# pwmdrive_2014_001.net
KiCad netlist of a schematic drawn in EAGLE
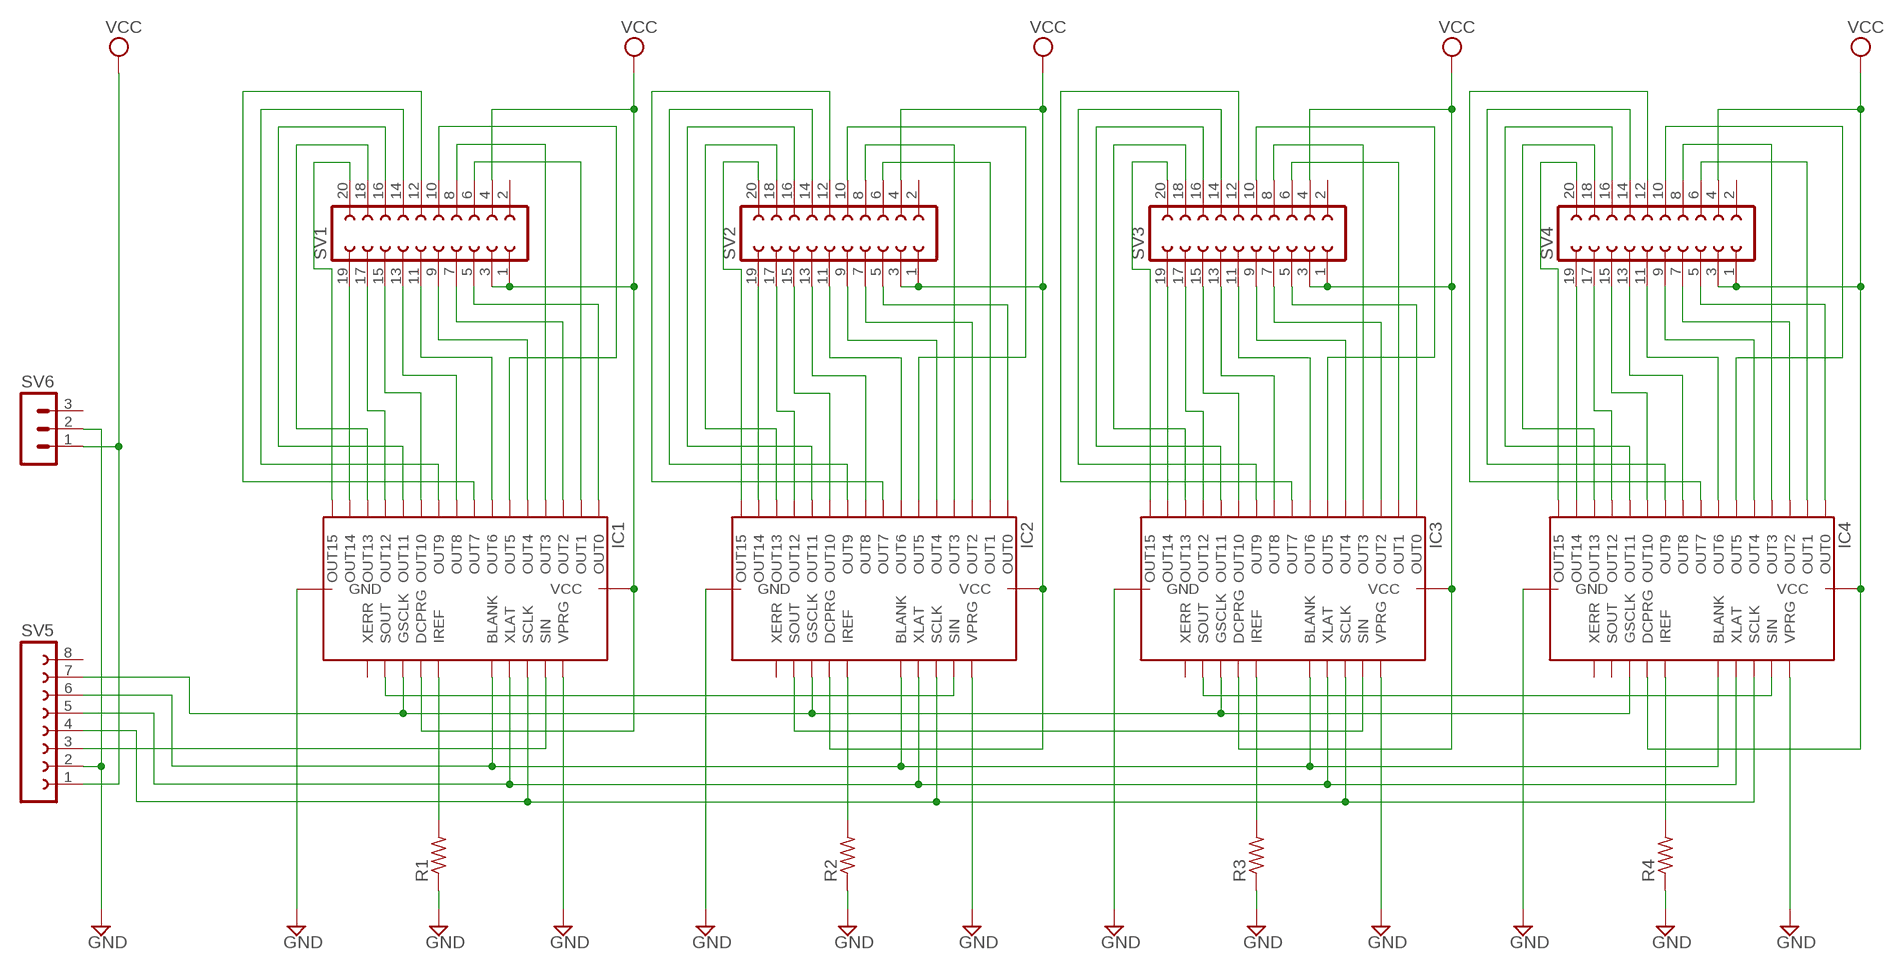
[diagram p0: schematic, sheet 1]

(export (version "E")
  (design (tool "Eeschema 10.0.6"))
  (components
    (comp (ref "IC1")
      (value "IC-PACKAGE_DIL28")
      (footprint "eagle-import:IC-PACKAGE_DIL28-6")
      (libsource (lib "eagle-import") (part "IC-PACKAGE_DIL28"))
    )
    (comp (ref "IC2")
      (value "IC-PACKAGE_DIL28")
      (footprint "eagle-import:IC-PACKAGE_DIL28-6")
      (libsource (lib "eagle-import") (part "IC-PACKAGE_DIL28"))
    )
    (comp (ref "IC3")
      (value "IC-PACKAGE_DIL28")
      (footprint "eagle-import:IC-PACKAGE_DIL28-6")
      (libsource (lib "eagle-import") (part "IC-PACKAGE_DIL28"))
    )
    (comp (ref "IC4")
      (value "IC-PACKAGE_DIL28")
      (footprint "eagle-import:IC-PACKAGE_DIL28-6")
      (libsource (lib "eagle-import") (part "IC-PACKAGE_DIL28"))
    )
    (comp (ref "R1")
      (value "R-US_0204/7")
      (footprint "eagle-import:0204_7")
      (libsource (lib "eagle-import") (part "R-US_0204/7"))
    )
    (comp (ref "R2")
      (value "R-US_0204/7")
      (footprint "eagle-import:0204_7")
      (libsource (lib "eagle-import") (part "R-US_0204/7"))
    )
    (comp (ref "R3")
      (value "R-US_0204/7")
      (footprint "eagle-import:0204_7")
      (libsource (lib "eagle-import") (part "R-US_0204/7"))
    )
    (comp (ref "R4")
      (value "R-US_0204/7")
      (footprint "eagle-import:0204_7")
      (libsource (lib "eagle-import") (part "R-US_0204/7"))
    )
    (comp (ref "SV1")
      (value "FE10-2")
      (footprint "eagle-import:FE10-2")
      (libsource (lib "eagle-import") (part "FE10-2"))
    )
    (comp (ref "SV2")
      (value "FE10-2")
      (footprint "eagle-import:FE10-2")
      (libsource (lib "eagle-import") (part "FE10-2"))
    )
    (comp (ref "SV3")
      (value "FE10-2")
      (footprint "eagle-import:FE10-2")
      (libsource (lib "eagle-import") (part "FE10-2"))
    )
    (comp (ref "SV4")
      (value "FE10-2")
      (footprint "eagle-import:FE10-2")
      (libsource (lib "eagle-import") (part "FE10-2"))
    )
    (comp (ref "SV5")
      (value "FE08-1")
      (footprint "eagle-import:FE08")
      (libsource (lib "eagle-import") (part "FE08-1"))
    )
    (comp (ref "SV6")
      (value "MA03-1")
      (footprint "eagle-import:MA03-1")
      (libsource (lib "eagle-import") (part "MA03-1"))
    )
  )
  (nets
    (net (code "1") (name "GND") (class "Default")
      (node (ref "IC1") (pin "22") (pinfunction "GND_22") (pintype "power_in"))
      (node (ref "IC1") (pin "27") (pinfunction "VPRG_27") (pintype "input"))
      (node (ref "IC2") (pin "22") (pinfunction "GND_22") (pintype "power_in"))
      (node (ref "IC2") (pin "27") (pinfunction "VPRG_27") (pintype "input"))
      (node (ref "IC3") (pin "22") (pinfunction "GND_22") (pintype "power_in"))
      (node (ref "IC3") (pin "27") (pinfunction "VPRG_27") (pintype "input"))
      (node (ref "IC4") (pin "22") (pinfunction "GND_22") (pintype "power_in"))
      (node (ref "IC4") (pin "27") (pinfunction "VPRG_27") (pintype "input"))
      (node (ref "R1") (pin "1") (pinfunction "1_1") (pintype "passive"))
      (node (ref "R2") (pin "1") (pinfunction "1_1") (pintype "passive"))
      (node (ref "R3") (pin "1") (pinfunction "1_1") (pintype "passive"))
      (node (ref "R4") (pin "1") (pinfunction "1_1") (pintype "passive"))
      (node (ref "SV5") (pin "2") (pinfunction "2_2") (pintype "passive"))
      (node (ref "SV6") (pin "2") (pinfunction "2_2") (pintype "passive"))
    )
    (net (code "2") (name "Net-(IC1-BLANK)") (class "Default")
      (node (ref "IC1") (pin "23") (pinfunction "BLANK_23") (pintype "input"))
      (node (ref "IC2") (pin "23") (pinfunction "BLANK_23") (pintype "input"))
      (node (ref "IC3") (pin "23") (pinfunction "BLANK_23") (pintype "input"))
      (node (ref "IC4") (pin "23") (pinfunction "BLANK_23") (pintype "input"))
      (node (ref "SV5") (pin "6") (pinfunction "6_6") (pintype "passive"))
    )
    (net (code "3") (name "Net-(IC1-GSCLK)") (class "Default")
      (node (ref "IC1") (pin "18") (pinfunction "GSCLK_18") (pintype "input"))
      (node (ref "IC2") (pin "18") (pinfunction "GSCLK_18") (pintype "input"))
      (node (ref "IC3") (pin "18") (pinfunction "GSCLK_18") (pintype "input"))
      (node (ref "IC4") (pin "18") (pinfunction "GSCLK_18") (pintype "input"))
      (node (ref "SV5") (pin "7") (pinfunction "7_7") (pintype "passive"))
    )
    (net (code "4") (name "Net-(IC1-IREF)") (class "Default")
      (node (ref "IC1") (pin "20") (pinfunction "IREF_20") (pintype "passive"))
      (node (ref "R1") (pin "2") (pinfunction "2_2") (pintype "passive"))
    )
    (net (code "5") (name "Net-(IC1-OUT0)") (class "Default")
      (node (ref "IC1") (pin "28") (pinfunction "OUT0_28") (pintype "open_collector"))
      (node (ref "SV1") (pin "5") (pinfunction "5_5") (pintype "passive"))
    )
    (net (code "6") (name "Net-(IC1-OUT1)") (class "Default")
      (node (ref "IC1") (pin "1") (pinfunction "OUT1_1") (pintype "open_collector"))
      (node (ref "SV1") (pin "6") (pinfunction "6_6") (pintype "passive"))
    )
    (net (code "7") (name "Net-(IC1-OUT2)") (class "Default")
      (node (ref "IC1") (pin "2") (pinfunction "OUT2_2") (pintype "open_collector"))
      (node (ref "SV1") (pin "7") (pinfunction "7_7") (pintype "passive"))
    )
    (net (code "8") (name "Net-(IC1-OUT3)") (class "Default")
      (node (ref "IC1") (pin "3") (pinfunction "OUT3_3") (pintype "open_collector"))
      (node (ref "SV1") (pin "8") (pinfunction "8_8") (pintype "passive"))
    )
    (net (code "9") (name "Net-(IC1-OUT4)") (class "Default")
      (node (ref "IC1") (pin "4") (pinfunction "OUT4_4") (pintype "open_collector"))
      (node (ref "SV1") (pin "9") (pinfunction "9_9") (pintype "passive"))
    )
    (net (code "10") (name "Net-(IC1-OUT5)") (class "Default")
      (node (ref "IC1") (pin "5") (pinfunction "OUT5_5") (pintype "open_collector"))
      (node (ref "SV1") (pin "10") (pinfunction "10_10") (pintype "passive"))
    )
    (net (code "11") (name "Net-(IC1-OUT6)") (class "Default")
      (node (ref "IC1") (pin "6") (pinfunction "OUT6_6") (pintype "open_collector"))
      (node (ref "SV1") (pin "11") (pinfunction "11_11") (pintype "passive"))
    )
    (net (code "12") (name "Net-(IC1-OUT7)") (class "Default")
      (node (ref "IC1") (pin "7") (pinfunction "OUT7_7") (pintype "open_collector"))
      (node (ref "SV1") (pin "12") (pinfunction "12_12") (pintype "passive"))
    )
    (net (code "13") (name "Net-(IC1-OUT8)") (class "Default")
      (node (ref "IC1") (pin "8") (pinfunction "OUT8_8") (pintype "open_collector"))
      (node (ref "SV1") (pin "13") (pinfunction "13_13") (pintype "passive"))
    )
    (net (code "14") (name "Net-(IC1-OUT9)") (class "Default")
      (node (ref "IC1") (pin "9") (pinfunction "OUT9_9") (pintype "open_collector"))
      (node (ref "SV1") (pin "14") (pinfunction "14_14") (pintype "passive"))
    )
    (net (code "15") (name "Net-(IC1-OUT10)") (class "Default")
      (node (ref "IC1") (pin "10") (pinfunction "OUT10_10") (pintype "open_collector"))
      (node (ref "SV1") (pin "15") (pinfunction "15_15") (pintype "passive"))
    )
    (net (code "16") (name "Net-(IC1-OUT11)") (class "Default")
      (node (ref "IC1") (pin "11") (pinfunction "OUT11_11") (pintype "open_collector"))
      (node (ref "SV1") (pin "16") (pinfunction "16_16") (pintype "passive"))
    )
    (net (code "17") (name "Net-(IC1-OUT12)") (class "Default")
      (node (ref "IC1") (pin "12") (pinfunction "OUT12_12") (pintype "open_collector"))
      (node (ref "SV1") (pin "17") (pinfunction "17_17") (pintype "passive"))
    )
    (net (code "18") (name "Net-(IC1-OUT13)") (class "Default")
      (node (ref "IC1") (pin "13") (pinfunction "OUT13_13") (pintype "open_collector"))
      (node (ref "SV1") (pin "18") (pinfunction "18_18") (pintype "passive"))
    )
    (net (code "19") (name "Net-(IC1-OUT14)") (class "Default")
      (node (ref "IC1") (pin "14") (pinfunction "OUT14_14") (pintype "open_collector"))
      (node (ref "SV1") (pin "19") (pinfunction "19_19") (pintype "passive"))
    )
    (net (code "20") (name "Net-(IC1-OUT15)") (class "Default")
      (node (ref "IC1") (pin "15") (pinfunction "OUT15_15") (pintype "open_collector"))
      (node (ref "SV1") (pin "20") (pinfunction "20_20") (pintype "passive"))
    )
    (net (code "21") (name "Net-(IC1-SCLK)") (class "Default")
      (node (ref "IC1") (pin "25") (pinfunction "SCLK_25") (pintype "input"))
      (node (ref "IC2") (pin "25") (pinfunction "SCLK_25") (pintype "input"))
      (node (ref "IC3") (pin "25") (pinfunction "SCLK_25") (pintype "input"))
      (node (ref "IC4") (pin "25") (pinfunction "SCLK_25") (pintype "input"))
      (node (ref "SV5") (pin "4") (pinfunction "4_4") (pintype "passive"))
    )
    (net (code "22") (name "Net-(IC1-SIN)") (class "Default")
      (node (ref "IC1") (pin "26") (pinfunction "SIN_26") (pintype "input"))
      (node (ref "SV5") (pin "3") (pinfunction "3_3") (pintype "passive"))
    )
    (net (code "23") (name "Net-(IC1-SOUT)") (class "Default")
      (node (ref "IC1") (pin "17") (pinfunction "SOUT_17") (pintype "output"))
      (node (ref "IC2") (pin "26") (pinfunction "SIN_26") (pintype "input"))
    )
    (net (code "24") (name "Net-(IC1-XLAT)") (class "Default")
      (node (ref "IC1") (pin "24") (pinfunction "XLAT_24") (pintype "input"))
      (node (ref "IC2") (pin "24") (pinfunction "XLAT_24") (pintype "input"))
      (node (ref "IC3") (pin "24") (pinfunction "XLAT_24") (pintype "input"))
      (node (ref "IC4") (pin "24") (pinfunction "XLAT_24") (pintype "input"))
      (node (ref "SV5") (pin "5") (pinfunction "5_5") (pintype "passive"))
    )
    (net (code "25") (name "Net-(IC2-IREF)") (class "Default")
      (node (ref "IC2") (pin "20") (pinfunction "IREF_20") (pintype "passive"))
      (node (ref "R2") (pin "2") (pinfunction "2_2") (pintype "passive"))
    )
    (net (code "26") (name "Net-(IC2-OUT0)") (class "Default")
      (node (ref "IC2") (pin "28") (pinfunction "OUT0_28") (pintype "open_collector"))
      (node (ref "SV2") (pin "5") (pinfunction "5_5") (pintype "passive"))
    )
    (net (code "27") (name "Net-(IC2-OUT1)") (class "Default")
      (node (ref "IC2") (pin "1") (pinfunction "OUT1_1") (pintype "open_collector"))
      (node (ref "SV2") (pin "6") (pinfunction "6_6") (pintype "passive"))
    )
    (net (code "28") (name "Net-(IC2-OUT2)") (class "Default")
      (node (ref "IC2") (pin "2") (pinfunction "OUT2_2") (pintype "open_collector"))
      (node (ref "SV2") (pin "7") (pinfunction "7_7") (pintype "passive"))
    )
    (net (code "29") (name "Net-(IC2-OUT3)") (class "Default")
      (node (ref "IC2") (pin "3") (pinfunction "OUT3_3") (pintype "open_collector"))
      (node (ref "SV2") (pin "8") (pinfunction "8_8") (pintype "passive"))
    )
    (net (code "30") (name "Net-(IC2-OUT4)") (class "Default")
      (node (ref "IC2") (pin "4") (pinfunction "OUT4_4") (pintype "open_collector"))
      (node (ref "SV2") (pin "9") (pinfunction "9_9") (pintype "passive"))
    )
    (net (code "31") (name "Net-(IC2-OUT5)") (class "Default")
      (node (ref "IC2") (pin "5") (pinfunction "OUT5_5") (pintype "open_collector"))
      (node (ref "SV2") (pin "10") (pinfunction "10_10") (pintype "passive"))
    )
    (net (code "32") (name "Net-(IC2-OUT6)") (class "Default")
      (node (ref "IC2") (pin "6") (pinfunction "OUT6_6") (pintype "open_collector"))
      (node (ref "SV2") (pin "11") (pinfunction "11_11") (pintype "passive"))
    )
    (net (code "33") (name "Net-(IC2-OUT7)") (class "Default")
      (node (ref "IC2") (pin "7") (pinfunction "OUT7_7") (pintype "open_collector"))
      (node (ref "SV2") (pin "12") (pinfunction "12_12") (pintype "passive"))
    )
    (net (code "34") (name "Net-(IC2-OUT8)") (class "Default")
      (node (ref "IC2") (pin "8") (pinfunction "OUT8_8") (pintype "open_collector"))
      (node (ref "SV2") (pin "13") (pinfunction "13_13") (pintype "passive"))
    )
    (net (code "35") (name "Net-(IC2-OUT9)") (class "Default")
      (node (ref "IC2") (pin "9") (pinfunction "OUT9_9") (pintype "open_collector"))
      (node (ref "SV2") (pin "14") (pinfunction "14_14") (pintype "passive"))
    )
    (net (code "36") (name "Net-(IC2-OUT10)") (class "Default")
      (node (ref "IC2") (pin "10") (pinfunction "OUT10_10") (pintype "open_collector"))
      (node (ref "SV2") (pin "15") (pinfunction "15_15") (pintype "passive"))
    )
    (net (code "37") (name "Net-(IC2-OUT11)") (class "Default")
      (node (ref "IC2") (pin "11") (pinfunction "OUT11_11") (pintype "open_collector"))
      (node (ref "SV2") (pin "16") (pinfunction "16_16") (pintype "passive"))
    )
    (net (code "38") (name "Net-(IC2-OUT12)") (class "Default")
      (node (ref "IC2") (pin "12") (pinfunction "OUT12_12") (pintype "open_collector"))
      (node (ref "SV2") (pin "17") (pinfunction "17_17") (pintype "passive"))
    )
    (net (code "39") (name "Net-(IC2-OUT13)") (class "Default")
      (node (ref "IC2") (pin "13") (pinfunction "OUT13_13") (pintype "open_collector"))
      (node (ref "SV2") (pin "18") (pinfunction "18_18") (pintype "passive"))
    )
    (net (code "40") (name "Net-(IC2-OUT14)") (class "Default")
      (node (ref "IC2") (pin "14") (pinfunction "OUT14_14") (pintype "open_collector"))
      (node (ref "SV2") (pin "19") (pinfunction "19_19") (pintype "passive"))
    )
    (net (code "41") (name "Net-(IC2-OUT15)") (class "Default")
      (node (ref "IC2") (pin "15") (pinfunction "OUT15_15") (pintype "open_collector"))
      (node (ref "SV2") (pin "20") (pinfunction "20_20") (pintype "passive"))
    )
    (net (code "42") (name "Net-(IC2-SOUT)") (class "Default")
      (node (ref "IC2") (pin "17") (pinfunction "SOUT_17") (pintype "output"))
      (node (ref "IC3") (pin "26") (pinfunction "SIN_26") (pintype "input"))
    )
    (net (code "43") (name "Net-(IC3-IREF)") (class "Default")
      (node (ref "IC3") (pin "20") (pinfunction "IREF_20") (pintype "passive"))
      (node (ref "R3") (pin "2") (pinfunction "2_2") (pintype "passive"))
    )
    (net (code "44") (name "Net-(IC3-OUT0)") (class "Default")
      (node (ref "IC3") (pin "28") (pinfunction "OUT0_28") (pintype "open_collector"))
      (node (ref "SV3") (pin "5") (pinfunction "5_5") (pintype "passive"))
    )
    (net (code "45") (name "Net-(IC3-OUT1)") (class "Default")
      (node (ref "IC3") (pin "1") (pinfunction "OUT1_1") (pintype "open_collector"))
      (node (ref "SV3") (pin "6") (pinfunction "6_6") (pintype "passive"))
    )
    (net (code "46") (name "Net-(IC3-OUT2)") (class "Default")
      (node (ref "IC3") (pin "2") (pinfunction "OUT2_2") (pintype "open_collector"))
      (node (ref "SV3") (pin "7") (pinfunction "7_7") (pintype "passive"))
    )
    (net (code "47") (name "Net-(IC3-OUT3)") (class "Default")
      (node (ref "IC3") (pin "3") (pinfunction "OUT3_3") (pintype "open_collector"))
      (node (ref "SV3") (pin "8") (pinfunction "8_8") (pintype "passive"))
    )
    (net (code "48") (name "Net-(IC3-OUT4)") (class "Default")
      (node (ref "IC3") (pin "4") (pinfunction "OUT4_4") (pintype "open_collector"))
      (node (ref "SV3") (pin "9") (pinfunction "9_9") (pintype "passive"))
    )
    (net (code "49") (name "Net-(IC3-OUT5)") (class "Default")
      (node (ref "IC3") (pin "5") (pinfunction "OUT5_5") (pintype "open_collector"))
      (node (ref "SV3") (pin "10") (pinfunction "10_10") (pintype "passive"))
    )
    (net (code "50") (name "Net-(IC3-OUT6)") (class "Default")
      (node (ref "IC3") (pin "6") (pinfunction "OUT6_6") (pintype "open_collector"))
      (node (ref "SV3") (pin "11") (pinfunction "11_11") (pintype "passive"))
    )
    (net (code "51") (name "Net-(IC3-OUT7)") (class "Default")
      (node (ref "IC3") (pin "7") (pinfunction "OUT7_7") (pintype "open_collector"))
      (node (ref "SV3") (pin "12") (pinfunction "12_12") (pintype "passive"))
    )
    (net (code "52") (name "Net-(IC3-OUT8)") (class "Default")
      (node (ref "IC3") (pin "8") (pinfunction "OUT8_8") (pintype "open_collector"))
      (node (ref "SV3") (pin "13") (pinfunction "13_13") (pintype "passive"))
    )
    (net (code "53") (name "Net-(IC3-OUT9)") (class "Default")
      (node (ref "IC3") (pin "9") (pinfunction "OUT9_9") (pintype "open_collector"))
      (node (ref "SV3") (pin "14") (pinfunction "14_14") (pintype "passive"))
    )
    (net (code "54") (name "Net-(IC3-OUT10)") (class "Default")
      (node (ref "IC3") (pin "10") (pinfunction "OUT10_10") (pintype "open_collector"))
      (node (ref "SV3") (pin "15") (pinfunction "15_15") (pintype "passive"))
    )
    (net (code "55") (name "Net-(IC3-OUT11)") (class "Default")
      (node (ref "IC3") (pin "11") (pinfunction "OUT11_11") (pintype "open_collector"))
      (node (ref "SV3") (pin "16") (pinfunction "16_16") (pintype "passive"))
    )
    (net (code "56") (name "Net-(IC3-OUT12)") (class "Default")
      (node (ref "IC3") (pin "12") (pinfunction "OUT12_12") (pintype "open_collector"))
      (node (ref "SV3") (pin "17") (pinfunction "17_17") (pintype "passive"))
    )
    (net (code "57") (name "Net-(IC3-OUT13)") (class "Default")
      (node (ref "IC3") (pin "13") (pinfunction "OUT13_13") (pintype "open_collector"))
      (node (ref "SV3") (pin "18") (pinfunction "18_18") (pintype "passive"))
    )
    (net (code "58") (name "Net-(IC3-OUT14)") (class "Default")
      (node (ref "IC3") (pin "14") (pinfunction "OUT14_14") (pintype "open_collector"))
      (node (ref "SV3") (pin "19") (pinfunction "19_19") (pintype "passive"))
    )
    (net (code "59") (name "Net-(IC3-OUT15)") (class "Default")
      (node (ref "IC3") (pin "15") (pinfunction "OUT15_15") (pintype "open_collector"))
      (node (ref "SV3") (pin "20") (pinfunction "20_20") (pintype "passive"))
    )
    (net (code "60") (name "Net-(IC3-SOUT)") (class "Default")
      (node (ref "IC3") (pin "17") (pinfunction "SOUT_17") (pintype "output"))
      (node (ref "IC4") (pin "26") (pinfunction "SIN_26") (pintype "input"))
    )
    (net (code "61") (name "Net-(IC4-IREF)") (class "Default")
      (node (ref "IC4") (pin "20") (pinfunction "IREF_20") (pintype "passive"))
      (node (ref "R4") (pin "2") (pinfunction "2_2") (pintype "passive"))
    )
    (net (code "62") (name "Net-(IC4-OUT0)") (class "Default")
      (node (ref "IC4") (pin "28") (pinfunction "OUT0_28") (pintype "open_collector"))
      (node (ref "SV4") (pin "5") (pinfunction "5_5") (pintype "passive"))
    )
    (net (code "63") (name "Net-(IC4-OUT1)") (class "Default")
      (node (ref "IC4") (pin "1") (pinfunction "OUT1_1") (pintype "open_collector"))
      (node (ref "SV4") (pin "6") (pinfunction "6_6") (pintype "passive"))
    )
    (net (code "64") (name "Net-(IC4-OUT2)") (class "Default")
      (node (ref "IC4") (pin "2") (pinfunction "OUT2_2") (pintype "open_collector"))
      (node (ref "SV4") (pin "7") (pinfunction "7_7") (pintype "passive"))
    )
    (net (code "65") (name "Net-(IC4-OUT3)") (class "Default")
      (node (ref "IC4") (pin "3") (pinfunction "OUT3_3") (pintype "open_collector"))
      (node (ref "SV4") (pin "8") (pinfunction "8_8") (pintype "passive"))
    )
    (net (code "66") (name "Net-(IC4-OUT4)") (class "Default")
      (node (ref "IC4") (pin "4") (pinfunction "OUT4_4") (pintype "open_collector"))
      (node (ref "SV4") (pin "9") (pinfunction "9_9") (pintype "passive"))
    )
    (net (code "67") (name "Net-(IC4-OUT5)") (class "Default")
      (node (ref "IC4") (pin "5") (pinfunction "OUT5_5") (pintype "open_collector"))
      (node (ref "SV4") (pin "10") (pinfunction "10_10") (pintype "passive"))
    )
    (net (code "68") (name "Net-(IC4-OUT6)") (class "Default")
      (node (ref "IC4") (pin "6") (pinfunction "OUT6_6") (pintype "open_collector"))
      (node (ref "SV4") (pin "11") (pinfunction "11_11") (pintype "passive"))
    )
    (net (code "69") (name "Net-(IC4-OUT7)") (class "Default")
      (node (ref "IC4") (pin "7") (pinfunction "OUT7_7") (pintype "open_collector"))
      (node (ref "SV4") (pin "12") (pinfunction "12_12") (pintype "passive"))
    )
    (net (code "70") (name "Net-(IC4-OUT8)") (class "Default")
      (node (ref "IC4") (pin "8") (pinfunction "OUT8_8") (pintype "open_collector"))
      (node (ref "SV4") (pin "13") (pinfunction "13_13") (pintype "passive"))
    )
    (net (code "71") (name "Net-(IC4-OUT9)") (class "Default")
      (node (ref "IC4") (pin "9") (pinfunction "OUT9_9") (pintype "open_collector"))
      (node (ref "SV4") (pin "14") (pinfunction "14_14") (pintype "passive"))
    )
    (net (code "72") (name "Net-(IC4-OUT10)") (class "Default")
      (node (ref "IC4") (pin "10") (pinfunction "OUT10_10") (pintype "open_collector"))
      (node (ref "SV4") (pin "15") (pinfunction "15_15") (pintype "passive"))
    )
    (net (code "73") (name "Net-(IC4-OUT11)") (class "Default")
      (node (ref "IC4") (pin "11") (pinfunction "OUT11_11") (pintype "open_collector"))
      (node (ref "SV4") (pin "16") (pinfunction "16_16") (pintype "passive"))
    )
    (net (code "74") (name "Net-(IC4-OUT12)") (class "Default")
      (node (ref "IC4") (pin "12") (pinfunction "OUT12_12") (pintype "open_collector"))
      (node (ref "SV4") (pin "17") (pinfunction "17_17") (pintype "passive"))
    )
    (net (code "75") (name "Net-(IC4-OUT13)") (class "Default")
      (node (ref "IC4") (pin "13") (pinfunction "OUT13_13") (pintype "open_collector"))
      (node (ref "SV4") (pin "18") (pinfunction "18_18") (pintype "passive"))
    )
    (net (code "76") (name "Net-(IC4-OUT14)") (class "Default")
      (node (ref "IC4") (pin "14") (pinfunction "OUT14_14") (pintype "open_collector"))
      (node (ref "SV4") (pin "19") (pinfunction "19_19") (pintype "passive"))
    )
    (net (code "77") (name "Net-(IC4-OUT15)") (class "Default")
      (node (ref "IC4") (pin "15") (pinfunction "OUT15_15") (pintype "open_collector"))
      (node (ref "SV4") (pin "20") (pinfunction "20_20") (pintype "passive"))
    )
    (net (code "78") (name "VCC") (class "Default")
      (node (ref "IC1") (pin "19") (pinfunction "DCPRG_19") (pintype "input"))
      (node (ref "IC1") (pin "21") (pinfunction "VCC_21") (pintype "power_in"))
      (node (ref "IC2") (pin "19") (pinfunction "DCPRG_19") (pintype "input"))
      (node (ref "IC2") (pin "21") (pinfunction "VCC_21") (pintype "power_in"))
      (node (ref "IC3") (pin "19") (pinfunction "DCPRG_19") (pintype "input"))
      (node (ref "IC3") (pin "21") (pinfunction "VCC_21") (pintype "power_in"))
      (node (ref "IC4") (pin "19") (pinfunction "DCPRG_19") (pintype "input"))
      (node (ref "IC4") (pin "21") (pinfunction "VCC_21") (pintype "power_in"))
      (node (ref "SV1") (pin "1") (pinfunction "1_1") (pintype "passive"))
      (node (ref "SV1") (pin "3") (pinfunction "3_3") (pintype "passive"))
      (node (ref "SV1") (pin "4") (pinfunction "4_4") (pintype "passive"))
      (node (ref "SV2") (pin "1") (pinfunction "1_1") (pintype "passive"))
      (node (ref "SV2") (pin "3") (pinfunction "3_3") (pintype "passive"))
      (node (ref "SV2") (pin "4") (pinfunction "4_4") (pintype "passive"))
      (node (ref "SV3") (pin "1") (pinfunction "1_1") (pintype "passive"))
      (node (ref "SV3") (pin "3") (pinfunction "3_3") (pintype "passive"))
      (node (ref "SV3") (pin "4") (pinfunction "4_4") (pintype "passive"))
      (node (ref "SV4") (pin "1") (pinfunction "1_1") (pintype "passive"))
      (node (ref "SV4") (pin "3") (pinfunction "3_3") (pintype "passive"))
      (node (ref "SV4") (pin "4") (pinfunction "4_4") (pintype "passive"))
      (node (ref "SV5") (pin "1") (pinfunction "1_1") (pintype "passive"))
      (node (ref "SV6") (pin "1") (pinfunction "1_1") (pintype "passive"))
    )
    (net (code "79") (name "unconnected-(IC1-XERR-Pad16)") (class "Default")
      (node (ref "IC1") (pin "16") (pinfunction "XERR_16") (pintype "open_collector"))
    )
    (net (code "80") (name "unconnected-(IC2-XERR-Pad16)") (class "Default")
      (node (ref "IC2") (pin "16") (pinfunction "XERR_16") (pintype "open_collector"))
    )
    (net (code "81") (name "unconnected-(IC3-XERR-Pad16)") (class "Default")
      (node (ref "IC3") (pin "16") (pinfunction "XERR_16") (pintype "open_collector"))
    )
    (net (code "82") (name "unconnected-(IC4-SOUT-Pad17)") (class "Default")
      (node (ref "IC4") (pin "17") (pinfunction "SOUT_17") (pintype "output"))
    )
    (net (code "83") (name "unconnected-(IC4-XERR-Pad16)") (class "Default")
      (node (ref "IC4") (pin "16") (pinfunction "XERR_16") (pintype "open_collector"))
    )
    (net (code "84") (name "unconnected-(SV1-Pad2)") (class "Default")
      (node (ref "SV1") (pin "2") (pinfunction "2_2") (pintype "passive"))
    )
    (net (code "85") (name "unconnected-(SV2-Pad2)") (class "Default")
      (node (ref "SV2") (pin "2") (pinfunction "2_2") (pintype "passive"))
    )
    (net (code "86") (name "unconnected-(SV3-Pad2)") (class "Default")
      (node (ref "SV3") (pin "2") (pinfunction "2_2") (pintype "passive"))
    )
    (net (code "87") (name "unconnected-(SV4-Pad2)") (class "Default")
      (node (ref "SV4") (pin "2") (pinfunction "2_2") (pintype "passive"))
    )
    (net (code "88") (name "unconnected-(SV5-Pad8)") (class "Default")
      (node (ref "SV5") (pin "8") (pinfunction "8_8") (pintype "passive"))
    )
    (net (code "89") (name "unconnected-(SV6-Pad3)") (class "Default")
      (node (ref "SV6") (pin "3") (pinfunction "3_3") (pintype "passive"))
    )
  )
)
